# Analog_inputs.net
KiCad netlist of a schematic drawn in Altium Designer
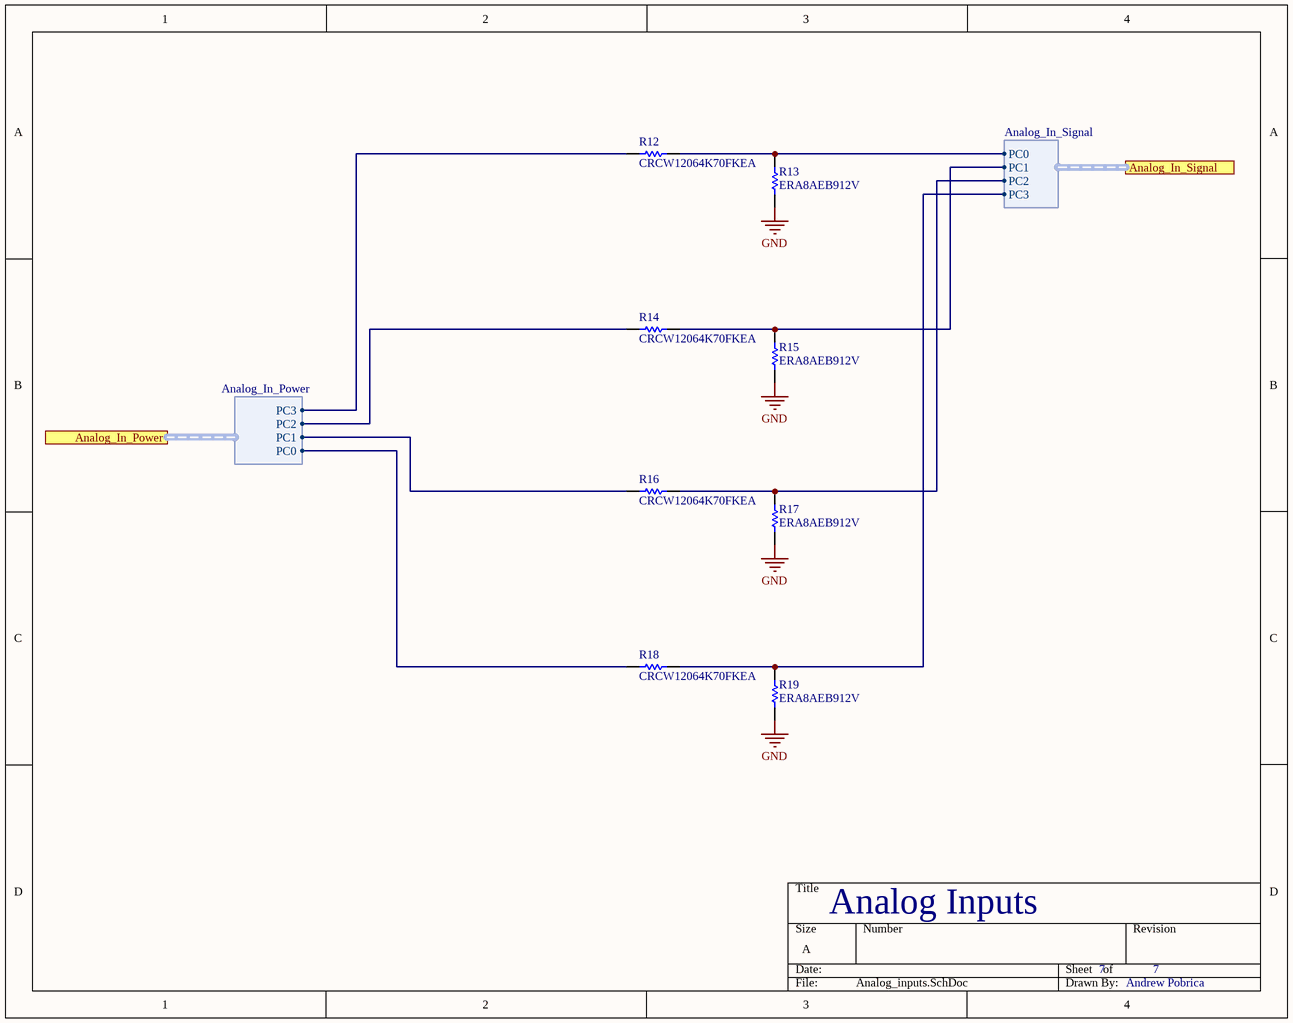
[diagram p0: Analog_inputs.SchDoc]

(export (version "E")
  (design (tool "Eeschema 10.0.6"))
  (components
    (comp (ref "R12")
      (value "CRCW12064K70FKEA")
      (footprint "RESC3216X60X45ML15T20")
      (description "Chip Resistor, 4.7 KOhm, +/- 1%, 0.25 W, -55 to 155 degC, 1206 (3216 Metric), RoHS, Tape and Reel")
      (fields (field (name "MANUFACTURER") "Vishay Semiconductor") (field (name "TOLERANCE") "1%"))
      (libsource (lib "Altium Content Vault") (part "RES-2"))
    )
    (comp (ref "R13")
      (value "ERA8AEB912V")
      (footprint "RESC3216X70X50ML20T25")
      (fields (field (name "MANUFACTURER") "Panasonic"))
      (libsource (lib "Altium Content Vault") (part "RES"))
    )
    (comp (ref "R14")
      (value "CRCW12064K70FKEA")
      (footprint "RESC3216X60X45ML15T20")
      (description "Chip Resistor, 4.7 KOhm, +/- 1%, 0.25 W, -55 to 155 degC, 1206 (3216 Metric), RoHS, Tape and Reel")
      (fields (field (name "MANUFACTURER") "Vishay Semiconductor") (field (name "TOLERANCE") "1%"))
      (libsource (lib "Altium Content Vault") (part "RES-2"))
    )
    (comp (ref "R15")
      (value "ERA8AEB912V")
      (footprint "RESC3216X70X50ML20T25")
      (fields (field (name "MANUFACTURER") "Panasonic"))
      (libsource (lib "Altium Content Vault") (part "RES"))
    )
    (comp (ref "R16")
      (value "CRCW12064K70FKEA")
      (footprint "RESC3216X60X45ML15T20")
      (description "Chip Resistor, 4.7 KOhm, +/- 1%, 0.25 W, -55 to 155 degC, 1206 (3216 Metric), RoHS, Tape and Reel")
      (fields (field (name "MANUFACTURER") "Vishay Semiconductor") (field (name "TOLERANCE") "1%"))
      (libsource (lib "Altium Content Vault") (part "RES-2"))
    )
    (comp (ref "R17")
      (value "ERA8AEB912V")
      (footprint "RESC3216X70X50ML20T25")
      (fields (field (name "MANUFACTURER") "Panasonic"))
      (libsource (lib "Altium Content Vault") (part "RES"))
    )
    (comp (ref "R18")
      (value "CRCW12064K70FKEA")
      (footprint "RESC3216X60X45ML15T20")
      (description "Chip Resistor, 4.7 KOhm, +/- 1%, 0.25 W, -55 to 155 degC, 1206 (3216 Metric), RoHS, Tape and Reel")
      (fields (field (name "MANUFACTURER") "Vishay Semiconductor") (field (name "TOLERANCE") "1%"))
      (libsource (lib "Altium Content Vault") (part "RES-2"))
    )
    (comp (ref "R19")
      (value "ERA8AEB912V")
      (footprint "RESC3216X70X50ML20T25")
      (fields (field (name "MANUFACTURER") "Panasonic"))
      (libsource (lib "Altium Content Vault") (part "RES"))
    )
  )
  (nets
    (net (code "5") (name "GND") (class "Default")
      (node (ref "R13") (pin "2") (pinfunction "2_2") (pintype "passive"))
      (node (ref "R15") (pin "2") (pinfunction "2_2") (pintype "passive"))
      (node (ref "R17") (pin "2") (pinfunction "2_2") (pintype "passive"))
      (node (ref "R19") (pin "2") (pinfunction "2_2") (pintype "passive"))
    )
    (net (code "6") (name "Net-(R12-Pad1)") (class "Default")
      (node (ref "R12") (pin "1") (pinfunction "1_1") (pintype "passive"))
      (node (ref "R13") (pin "1") (pinfunction "1_1") (pintype "passive"))
    )
    (net (code "7") (name "Net-(R14-Pad1)") (class "Default")
      (node (ref "R14") (pin "1") (pinfunction "1_1") (pintype "passive"))
      (node (ref "R15") (pin "1") (pinfunction "1_1") (pintype "passive"))
    )
    (net (code "8") (name "Net-(R16-Pad1)") (class "Default")
      (node (ref "R16") (pin "1") (pinfunction "1_1") (pintype "passive"))
      (node (ref "R17") (pin "1") (pinfunction "1_1") (pintype "passive"))
    )
    (net (code "9") (name "Net-(R18-Pad1)") (class "Default")
      (node (ref "R18") (pin "1") (pinfunction "1_1") (pintype "passive"))
      (node (ref "R19") (pin "1") (pinfunction "1_1") (pintype "passive"))
    )
    (net (code "10") (name "unconnected-(R12-Pad2)") (class "Default")
      (node (ref "R12") (pin "2") (pinfunction "2_2") (pintype "passive"))
    )
    (net (code "11") (name "unconnected-(R14-Pad2)") (class "Default")
      (node (ref "R14") (pin "2") (pinfunction "2_2") (pintype "passive"))
    )
    (net (code "12") (name "unconnected-(R16-Pad2)") (class "Default")
      (node (ref "R16") (pin "2") (pinfunction "2_2") (pintype "passive"))
    )
    (net (code "13") (name "unconnected-(R18-Pad2)") (class "Default")
      (node (ref "R18") (pin "2") (pinfunction "2_2") (pintype "passive"))
    )
  )
)
